# Source.net
KiCad netlist of a schematic drawn in Altium Designer
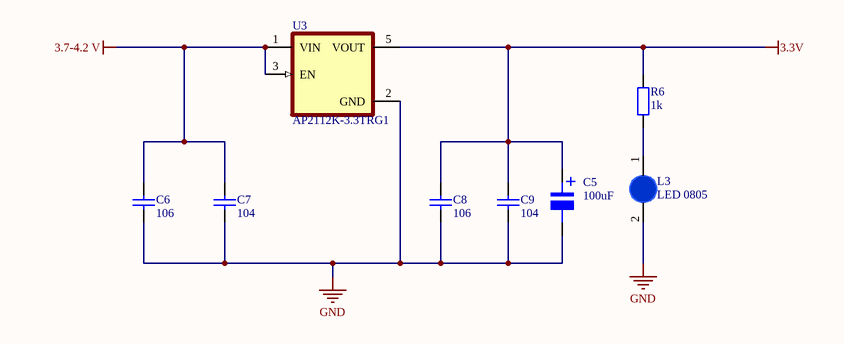
[diagram p0: Source.SchDoc]

(export (version "E")
  (design (tool "Eeschema 10.0.6"))
  (components
    (comp (ref "C5")
      (value "100uF")
      (footprint "tu nhom 6.3 (d)")
      (description "Dán")
      (libsource (lib "Altium_Lib_by_KhueNguyenCreator") (part "Tu Nhom 100uF 16V"))
    )
    (comp (ref "C6")
      (value "106")
      (footprint "tu 0805")
      (description "Dán")
      (libsource (lib "Altium_Lib_by_KhueNguyenCreator") (part "Tu 0805 106 16V 10%"))
    )
    (comp (ref "C7")
      (value "104")
      (footprint "tu 0805")
      (description "Dán")
      (libsource (lib "Altium_Lib_by_KhueNguyenCreator") (part "Tu 0805 106 16V 10%"))
    )
    (comp (ref "C8")
      (value "106")
      (footprint "tu 0805")
      (description "Dán")
      (libsource (lib "Altium_Lib_by_KhueNguyenCreator") (part "Tu 0805 106 16V 10%"))
    )
    (comp (ref "C9")
      (value "104")
      (footprint "tu 0805")
      (description "Dán")
      (libsource (lib "Altium_Lib_by_KhueNguyenCreator") (part "Tu 0805 106 16V 10%"))
    )
    (comp (ref "L3")
      (value "LED 0805")
      (footprint "LED-0805-Blue")
      (description "Dán")
      (libsource (lib "Altium_Lib_by_KhueNguyenCreator") (part "LED 0805 Xanh Duong"))
    )
    (comp (ref "R6")
      (value "1k")
      (footprint "tro smd 0805")
      (description "Dán")
      (libsource (lib "Altium_Lib_by_KhueNguyenCreator") (part "Tro 0805 5% 1k"))
    )
    (comp (ref "U3")
      (value "AP2112K-3.3TRG1")
      (footprint "SOT95P285X140-5N")
      (description "Linear Voltage Regulator IC Positive Fixed 1 Output 600mA SOT-25")
      (fields (field (name "MF") "Diodes Inc."))
      (libsource (lib "AP2112K-3.3TRG1") (part "AP2112K-3.3TRG1"))
    )
  )
  (nets
    (net (code "1") (name "3.3V") (class "Default")
      (node (ref "C5") (pin "1") (pinfunction "1_1") (pintype "passive"))
      (node (ref "C8") (pin "1") (pinfunction "1_1") (pintype "passive"))
      (node (ref "C9") (pin "1") (pinfunction "1_1") (pintype "passive"))
      (node (ref "R6") (pin "2") (pinfunction "2_2") (pintype "passive"))
      (node (ref "U3") (pin "5") (pinfunction "VOUT_5") (pintype "power_in"))
    )
    (net (code "2") (name "3.7-4.2 V") (class "Default")
      (node (ref "C6") (pin "1") (pinfunction "1_1") (pintype "passive"))
      (node (ref "C7") (pin "1") (pinfunction "1_1") (pintype "passive"))
      (node (ref "U3") (pin "1") (pinfunction "VIN_1") (pintype "power_in"))
      (node (ref "U3") (pin "3") (pinfunction "EN_3") (pintype "input"))
    )
    (net (code "3") (name "GND") (class "Default")
      (node (ref "C5") (pin "2") (pinfunction "2_2") (pintype "passive"))
      (node (ref "C6") (pin "2") (pinfunction "2_2") (pintype "passive"))
      (node (ref "C7") (pin "2") (pinfunction "2_2") (pintype "passive"))
      (node (ref "C8") (pin "2") (pinfunction "2_2") (pintype "passive"))
      (node (ref "C9") (pin "2") (pinfunction "2_2") (pintype "passive"))
      (node (ref "L3") (pin "2") (pinfunction "K_2") (pintype "passive"))
      (node (ref "U3") (pin "2") (pinfunction "GND_2") (pintype "power_in"))
    )
    (net (code "4") (name "Net-(L3-A)") (class "Default")
      (node (ref "L3") (pin "1") (pinfunction "A_1") (pintype "passive"))
      (node (ref "R6") (pin "1") (pinfunction "1_1") (pintype "passive"))
    )
  )
)
